# 12-Electrodes.net
KiCad netlist of a schematic drawn in Altium Designer
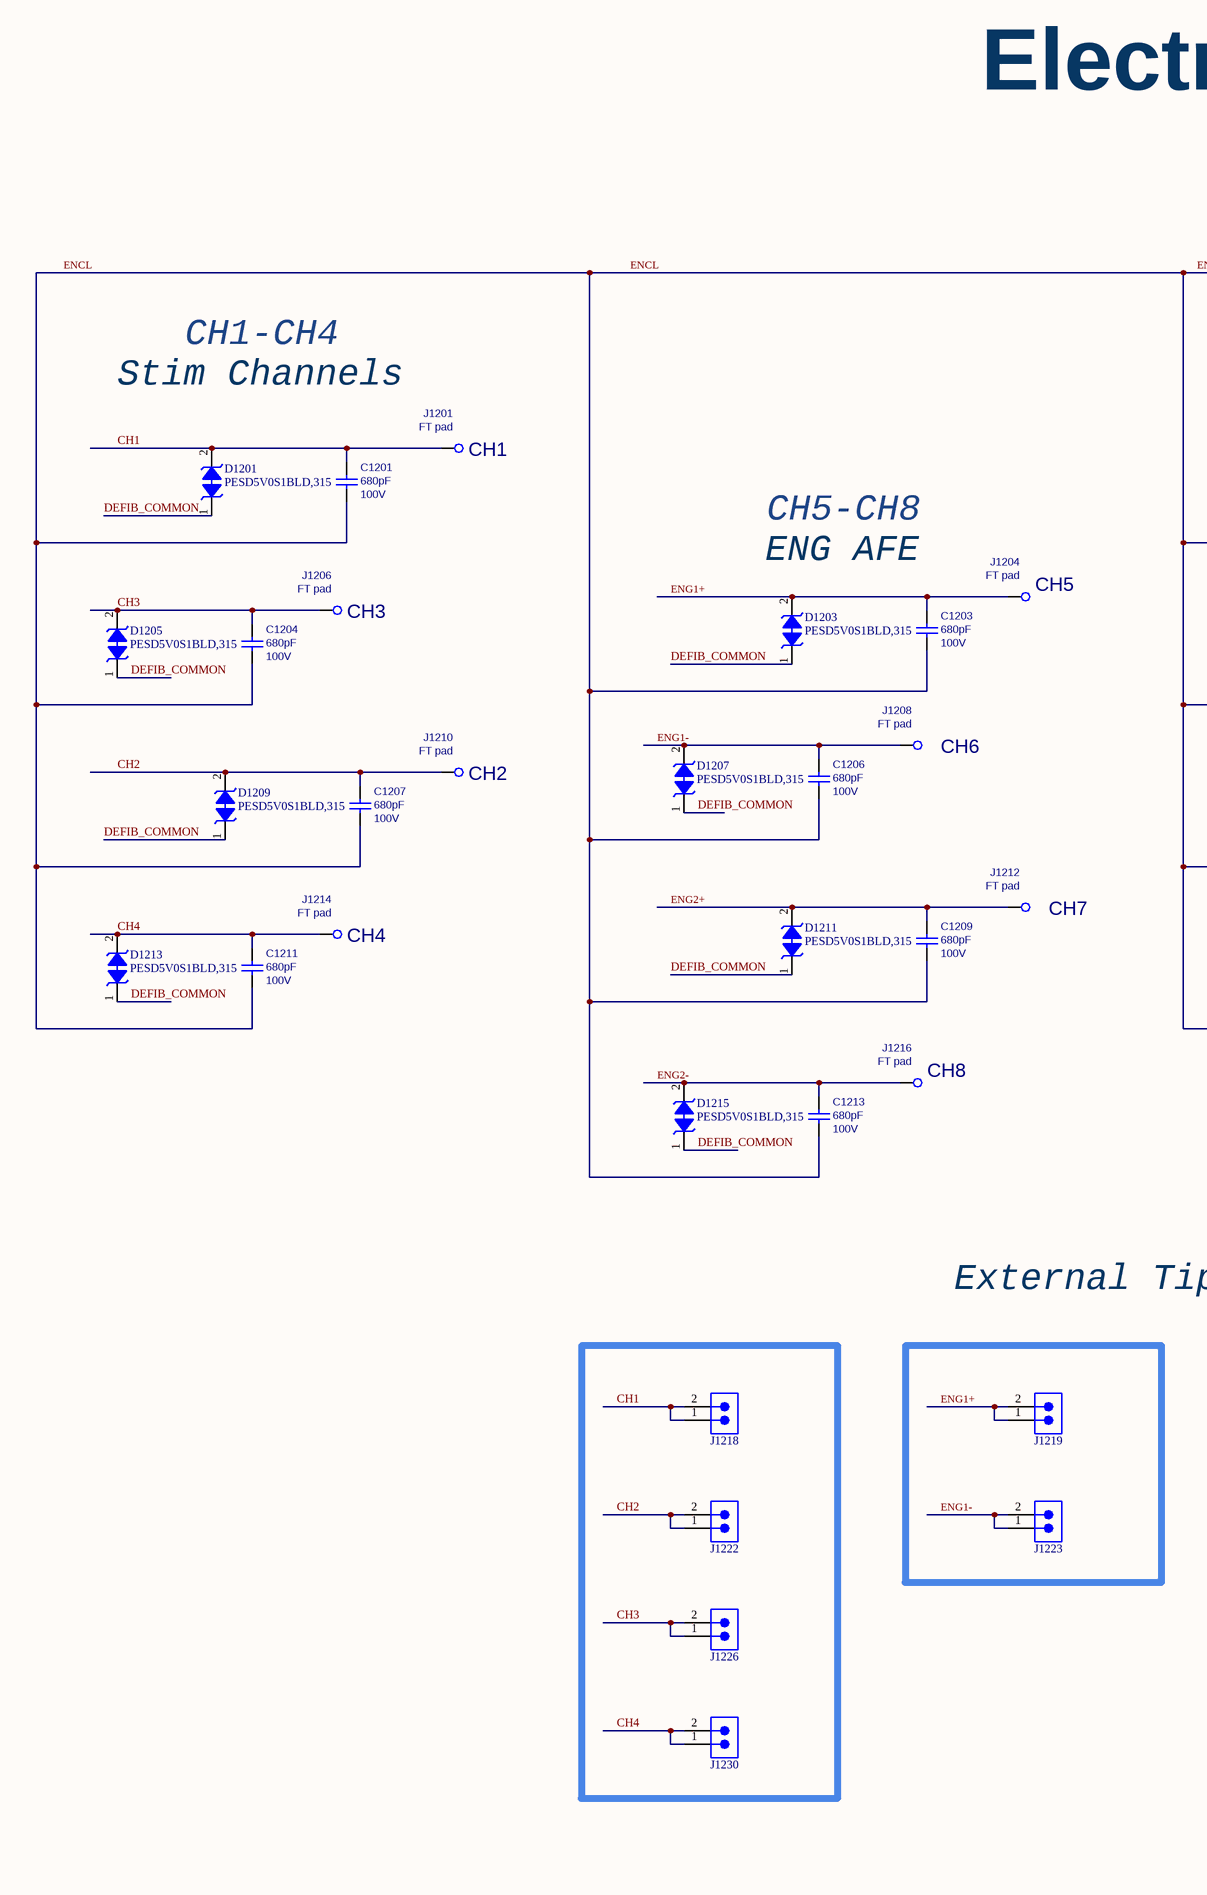
[diagram p0: 12-Electrodes.SchDoc, left]
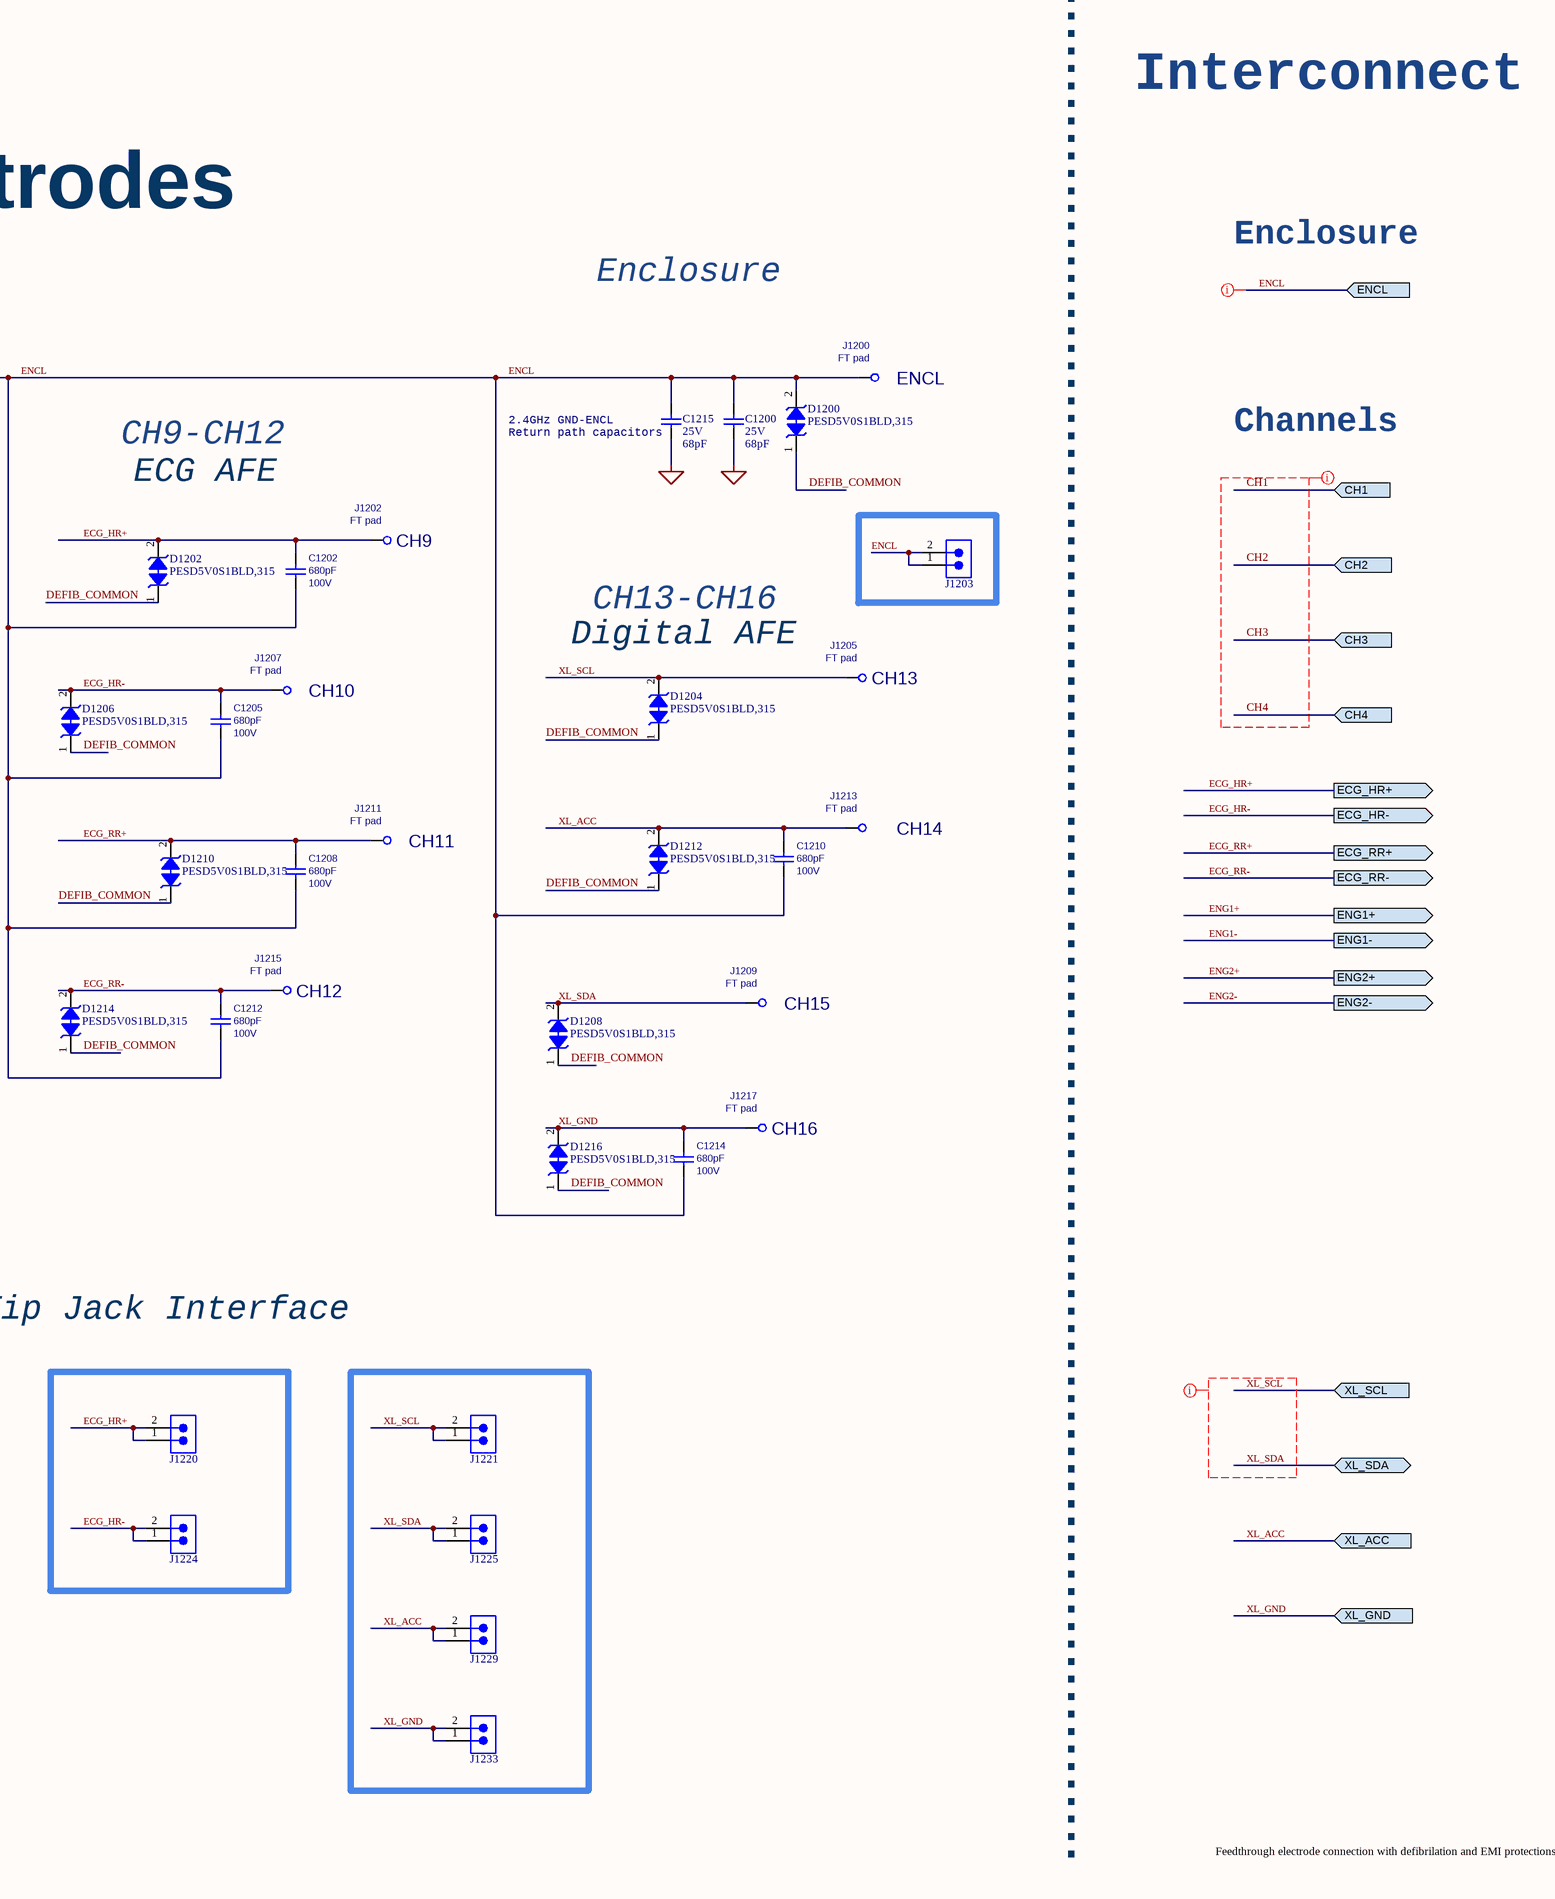
[diagram p1: 12-Electrodes.SchDoc, right]

(export (version "E")
  (design (tool "Eeschema 10.0.6"))
  (components
    (comp (ref "C1200")
      (value "68pF")
      (footprint "C0201_C")
      (description "Capacitor, 68pF, C0G, 25V, 5%, 0201, Implant-grade")
      (fields
        (field (name "MANUFACTURER") "Murata")
        (field (name "MANUFACTURER PART NUMBER") "GRT0335C1E680JA02D")
        (field (name "VOLTAGE RATING") "25V")
      )
      (libsource (lib "MP-LIBRARY") (part "GRT0335C1E680JA02D"))
    )
    (comp (ref "C1201")
      (value "680pF")
      (footprint "CAP0402_REDUCED")
      (description "Capacitor, 680pF, C0G, 100V, 5%, 0402")
      (fields
        (field (name "MANUFACTURER") "TDK")
        (field (name "RATING") "100V")
        (field (name "MANUFACTURER PART NUMBER") "C1005C0G2A681J050BE")
      )
      (libsource (lib "MP-LIBRARY") (part "C1005C0G2A681J050BE"))
    )
    (comp (ref "C1202")
      (value "680pF")
      (footprint "CAP0402_REDUCED")
      (description "Capacitor, 680pF, C0G, 100V, 5%, 0402")
      (fields
        (field (name "MANUFACTURER") "TDK")
        (field (name "RATING") "100V")
        (field (name "MANUFACTURER PART NUMBER") "C1005C0G2A681J050BE")
      )
      (libsource (lib "MP-LIBRARY") (part "C1005C0G2A681J050BE"))
    )
    (comp (ref "C1203")
      (value "680pF")
      (footprint "CAP0402_REDUCED")
      (description "Capacitor, 680pF, C0G, 100V, 5%, 0402")
      (fields
        (field (name "MANUFACTURER") "TDK")
        (field (name "RATING") "100V")
        (field (name "MANUFACTURER PART NUMBER") "C1005C0G2A681J050BE")
      )
      (libsource (lib "MP-LIBRARY") (part "C1005C0G2A681J050BE"))
    )
    (comp (ref "C1204")
      (value "680pF")
      (footprint "CAP0402_REDUCED")
      (description "Capacitor, 680pF, C0G, 100V, 5%, 0402")
      (fields
        (field (name "MANUFACTURER") "TDK")
        (field (name "RATING") "100V")
        (field (name "MANUFACTURER PART NUMBER") "C1005C0G2A681J050BE")
      )
      (libsource (lib "MP-LIBRARY") (part "C1005C0G2A681J050BE"))
    )
    (comp (ref "C1205")
      (value "680pF")
      (footprint "CAP0402_REDUCED")
      (description "Capacitor, 680pF, C0G, 100V, 5%, 0402")
      (fields
        (field (name "MANUFACTURER") "TDK")
        (field (name "RATING") "100V")
        (field (name "MANUFACTURER PART NUMBER") "C1005C0G2A681J050BE")
      )
      (libsource (lib "MP-LIBRARY") (part "C1005C0G2A681J050BE"))
    )
    (comp (ref "C1206")
      (value "680pF")
      (footprint "CAP0402_REDUCED")
      (description "Capacitor, 680pF, C0G, 100V, 5%, 0402")
      (fields
        (field (name "MANUFACTURER") "TDK")
        (field (name "RATING") "100V")
        (field (name "MANUFACTURER PART NUMBER") "C1005C0G2A681J050BE")
      )
      (libsource (lib "MP-LIBRARY") (part "C1005C0G2A681J050BE"))
    )
    (comp (ref "C1207")
      (value "680pF")
      (footprint "CAP0402_REDUCED")
      (description "Capacitor, 680pF, C0G, 100V, 5%, 0402")
      (fields
        (field (name "MANUFACTURER") "TDK")
        (field (name "RATING") "100V")
        (field (name "MANUFACTURER PART NUMBER") "C1005C0G2A681J050BE")
      )
      (libsource (lib "MP-LIBRARY") (part "C1005C0G2A681J050BE"))
    )
    (comp (ref "C1208")
      (value "680pF")
      (footprint "CAP0402_REDUCED")
      (description "Capacitor, 680pF, C0G, 100V, 5%, 0402")
      (fields
        (field (name "MANUFACTURER") "TDK")
        (field (name "RATING") "100V")
        (field (name "MANUFACTURER PART NUMBER") "C1005C0G2A681J050BE")
      )
      (libsource (lib "MP-LIBRARY") (part "C1005C0G2A681J050BE"))
    )
    (comp (ref "C1209")
      (value "680pF")
      (footprint "CAP0402_REDUCED")
      (description "Capacitor, 680pF, C0G, 100V, 5%, 0402")
      (fields
        (field (name "MANUFACTURER") "TDK")
        (field (name "RATING") "100V")
        (field (name "MANUFACTURER PART NUMBER") "C1005C0G2A681J050BE")
      )
      (libsource (lib "MP-LIBRARY") (part "C1005C0G2A681J050BE"))
    )
    (comp (ref "C1210")
      (value "680pF")
      (footprint "CAP0402_REDUCED")
      (description "Capacitor, 680pF, C0G, 100V, 5%, 0402")
      (fields
        (field (name "MANUFACTURER") "TDK")
        (field (name "RATING") "100V")
        (field (name "MANUFACTURER PART NUMBER") "C1005C0G2A681J050BE")
      )
      (libsource (lib "MP-LIBRARY") (part "C1005C0G2A681J050BE"))
    )
    (comp (ref "C1211")
      (value "680pF")
      (footprint "CAP0402_REDUCED")
      (description "Capacitor, 680pF, C0G, 100V, 5%, 0402")
      (fields
        (field (name "MANUFACTURER") "TDK")
        (field (name "RATING") "100V")
        (field (name "MANUFACTURER PART NUMBER") "C1005C0G2A681J050BE")
      )
      (libsource (lib "MP-LIBRARY") (part "C1005C0G2A681J050BE"))
    )
    (comp (ref "C1212")
      (value "680pF")
      (footprint "CAP0402_REDUCED")
      (description "Capacitor, 680pF, C0G, 100V, 5%, 0402")
      (fields
        (field (name "MANUFACTURER") "TDK")
        (field (name "RATING") "100V")
        (field (name "MANUFACTURER PART NUMBER") "C1005C0G2A681J050BE")
      )
      (libsource (lib "MP-LIBRARY") (part "C1005C0G2A681J050BE"))
    )
    (comp (ref "C1213")
      (value "680pF")
      (footprint "CAP0402_REDUCED")
      (description "Capacitor, 680pF, C0G, 100V, 5%, 0402")
      (fields
        (field (name "MANUFACTURER") "TDK")
        (field (name "RATING") "100V")
        (field (name "MANUFACTURER PART NUMBER") "C1005C0G2A681J050BE")
      )
      (libsource (lib "MP-LIBRARY") (part "C1005C0G2A681J050BE"))
    )
    (comp (ref "C1214")
      (value "680pF")
      (footprint "CAP0402_REDUCED")
      (description "Capacitor, 680pF, C0G, 100V, 5%, 0402")
      (fields
        (field (name "MANUFACTURER") "TDK")
        (field (name "RATING") "100V")
        (field (name "MANUFACTURER PART NUMBER") "C1005C0G2A681J050BE")
      )
      (libsource (lib "MP-LIBRARY") (part "C1005C0G2A681J050BE"))
    )
    (comp (ref "C1215")
      (value "68pF")
      (footprint "C0201_C")
      (description "Capacitor, 68pF, C0G, 25V, 5%, 0201, Implant-grade")
      (fields
        (field (name "MANUFACTURER") "Murata")
        (field (name "MANUFACTURER PART NUMBER") "GRT0335C1E680JA02D")
        (field (name "VOLTAGE RATING") "25V")
      )
      (libsource (lib "MP-LIBRARY") (part "GRT0335C1E680JA02D"))
    )
    (comp (ref "D1200")
      (value "PESD5V0S1BLD,315")
      (footprint "PESD5V0S1BLD315")
      (description "Diode ESD (Bi-directional)")
      (fields
        (field (name "MOUSER PART NUMBER") "771-PESD5V0S1BLD315")
        (field (name "MANUFACTURER") "Nexperia")
      )
      (libsource (lib "MP-LIBRARY") (part "PESD5V0S1BLD,315"))
    )
    (comp (ref "D1201")
      (value "PESD5V0S1BLD,315")
      (footprint "PESD5V0S1BLD315")
      (description "Diode ESD (Bi-directional)")
      (fields
        (field (name "MOUSER PART NUMBER") "771-PESD5V0S1BLD315")
        (field (name "MANUFACTURER") "Nexperia")
      )
      (libsource (lib "MP-LIBRARY") (part "PESD5V0S1BLD,315"))
    )
    (comp (ref "D1202")
      (value "PESD5V0S1BLD,315")
      (footprint "PESD5V0S1BLD315")
      (description "Diode ESD (Bi-directional)")
      (fields
        (field (name "MOUSER PART NUMBER") "771-PESD5V0S1BLD315")
        (field (name "MANUFACTURER") "Nexperia")
      )
      (libsource (lib "MP-LIBRARY") (part "PESD5V0S1BLD,315"))
    )
    (comp (ref "D1203")
      (value "PESD5V0S1BLD,315")
      (footprint "PESD5V0S1BLD315")
      (description "Diode ESD (Bi-directional)")
      (fields
        (field (name "MOUSER PART NUMBER") "771-PESD5V0S1BLD315")
        (field (name "MANUFACTURER") "Nexperia")
      )
      (libsource (lib "MP-LIBRARY") (part "PESD5V0S1BLD,315"))
    )
    (comp (ref "D1204")
      (value "PESD5V0S1BLD,315")
      (footprint "PESD5V0S1BLD315")
      (description "Diode ESD (Bi-directional)")
      (fields
        (field (name "MOUSER PART NUMBER") "771-PESD5V0S1BLD315")
        (field (name "MANUFACTURER") "Nexperia")
      )
      (libsource (lib "MP-LIBRARY") (part "PESD5V0S1BLD,315"))
    )
    (comp (ref "D1205")
      (value "PESD5V0S1BLD,315")
      (footprint "PESD5V0S1BLD315")
      (description "Diode ESD (Bi-directional)")
      (fields
        (field (name "MOUSER PART NUMBER") "771-PESD5V0S1BLD315")
        (field (name "MANUFACTURER") "Nexperia")
      )
      (libsource (lib "MP-LIBRARY") (part "PESD5V0S1BLD,315"))
    )
    (comp (ref "D1206")
      (value "PESD5V0S1BLD,315")
      (footprint "PESD5V0S1BLD315")
      (description "Diode ESD (Bi-directional)")
      (fields
        (field (name "MOUSER PART NUMBER") "771-PESD5V0S1BLD315")
        (field (name "MANUFACTURER") "Nexperia")
      )
      (libsource (lib "MP-LIBRARY") (part "PESD5V0S1BLD,315"))
    )
    (comp (ref "D1207")
      (value "PESD5V0S1BLD,315")
      (footprint "PESD5V0S1BLD315")
      (description "Diode ESD (Bi-directional)")
      (fields
        (field (name "MOUSER PART NUMBER") "771-PESD5V0S1BLD315")
        (field (name "MANUFACTURER") "Nexperia")
      )
      (libsource (lib "MP-LIBRARY") (part "PESD5V0S1BLD,315"))
    )
    (comp (ref "D1208")
      (value "PESD5V0S1BLD,315")
      (footprint "PESD5V0S1BLD315")
      (description "Diode ESD (Bi-directional)")
      (fields
        (field (name "MOUSER PART NUMBER") "771-PESD5V0S1BLD315")
        (field (name "MANUFACTURER") "Nexperia")
      )
      (libsource (lib "MP-LIBRARY") (part "PESD5V0S1BLD,315"))
    )
    (comp (ref "D1209")
      (value "PESD5V0S1BLD,315")
      (footprint "PESD5V0S1BLD315")
      (description "Diode ESD (Bi-directional)")
      (fields
        (field (name "MOUSER PART NUMBER") "771-PESD5V0S1BLD315")
        (field (name "MANUFACTURER") "Nexperia")
      )
      (libsource (lib "MP-LIBRARY") (part "PESD5V0S1BLD,315"))
    )
    (comp (ref "D1210")
      (value "PESD5V0S1BLD,315")
      (footprint "PESD5V0S1BLD315")
      (description "Diode ESD (Bi-directional)")
      (fields
        (field (name "MOUSER PART NUMBER") "771-PESD5V0S1BLD315")
        (field (name "MANUFACTURER") "Nexperia")
      )
      (libsource (lib "MP-LIBRARY") (part "PESD5V0S1BLD,315"))
    )
    (comp (ref "D1211")
      (value "PESD5V0S1BLD,315")
      (footprint "PESD5V0S1BLD315")
      (description "Diode ESD (Bi-directional)")
      (fields
        (field (name "MOUSER PART NUMBER") "771-PESD5V0S1BLD315")
        (field (name "MANUFACTURER") "Nexperia")
      )
      (libsource (lib "MP-LIBRARY") (part "PESD5V0S1BLD,315"))
    )
    (comp (ref "D1212")
      (value "PESD5V0S1BLD,315")
      (footprint "PESD5V0S1BLD315")
      (description "Diode ESD (Bi-directional)")
      (fields
        (field (name "MOUSER PART NUMBER") "771-PESD5V0S1BLD315")
        (field (name "MANUFACTURER") "Nexperia")
      )
      (libsource (lib "MP-LIBRARY") (part "PESD5V0S1BLD,315"))
    )
    (comp (ref "D1213")
      (value "PESD5V0S1BLD,315")
      (footprint "PESD5V0S1BLD315")
      (description "Diode ESD (Bi-directional)")
      (fields
        (field (name "MOUSER PART NUMBER") "771-PESD5V0S1BLD315")
        (field (name "MANUFACTURER") "Nexperia")
      )
      (libsource (lib "MP-LIBRARY") (part "PESD5V0S1BLD,315"))
    )
    (comp (ref "D1214")
      (value "PESD5V0S1BLD,315")
      (footprint "PESD5V0S1BLD315")
      (description "Diode ESD (Bi-directional)")
      (fields
        (field (name "MOUSER PART NUMBER") "771-PESD5V0S1BLD315")
        (field (name "MANUFACTURER") "Nexperia")
      )
      (libsource (lib "MP-LIBRARY") (part "PESD5V0S1BLD,315"))
    )
    (comp (ref "D1215")
      (value "PESD5V0S1BLD,315")
      (footprint "PESD5V0S1BLD315")
      (description "Diode ESD (Bi-directional)")
      (fields
        (field (name "MOUSER PART NUMBER") "771-PESD5V0S1BLD315")
        (field (name "MANUFACTURER") "Nexperia")
      )
      (libsource (lib "MP-LIBRARY") (part "PESD5V0S1BLD,315"))
    )
    (comp (ref "D1216")
      (value "PESD5V0S1BLD,315")
      (footprint "PESD5V0S1BLD315")
      (description "Diode ESD (Bi-directional)")
      (fields
        (field (name "MOUSER PART NUMBER") "771-PESD5V0S1BLD315")
        (field (name "MANUFACTURER") "Nexperia")
      )
      (libsource (lib "MP-LIBRARY") (part "PESD5V0S1BLD,315"))
    )
    (comp (ref "J1200")
      (value "FT pad")
      (footprint "FEEDHOLE_20mil")
      (description "FT pad, Thru-hole, 20 mil hole")
      (fields (field (name "Comment") "THPAD_20m"))
      (libsource (lib "MP-LIBRARY") (part "HOLE_20m"))
    )
    (comp (ref "J1201")
      (value "FT pad")
      (footprint "FEEDHOLE_20mil")
      (description "FT pad, Thru-hole, 20 mil hole")
      (fields (field (name "Comment") "THPAD_20m"))
      (libsource (lib "MP-LIBRARY") (part "HOLE_20m"))
    )
    (comp (ref "J1202")
      (value "FT pad")
      (footprint "FEEDHOLE_20mil")
      (description "FT pad, Thru-hole, 20 mil hole")
      (fields (field (name "Comment") "THPAD_20m"))
      (libsource (lib "MP-LIBRARY") (part "HOLE_20m"))
    )
    (comp (ref "J1203")
      (value "TSW-102-26-G-S")
      (footprint "SMTC-TSW-102-26-XX-S")
      (description "Conn Unshrouded Header HDR 2 POS 2.54mm Solder ST Thru-Hole")
      (fields (field (name "MANUFACTURER") "Samtec"))
      (libsource (lib "MP-LIBRARY") (part "TSW-102-26-G-S"))
    )
    (comp (ref "J1204")
      (value "FT pad")
      (footprint "FEEDHOLE_20mil")
      (description "FT pad, Thru-hole, 20 mil hole")
      (fields (field (name "Comment") "THPAD_20m"))
      (libsource (lib "MP-LIBRARY") (part "HOLE_20m"))
    )
    (comp (ref "J1205")
      (value "FT pad")
      (footprint "FEEDHOLE_20mil")
      (description "FT pad, Thru-hole, 20 mil hole")
      (fields (field (name "Comment") "THPAD_20m"))
      (libsource (lib "MP-LIBRARY") (part "HOLE_20m"))
    )
    (comp (ref "J1206")
      (value "FT pad")
      (footprint "FEEDHOLE_20mil")
      (description "FT pad, Thru-hole, 20 mil hole")
      (fields (field (name "Comment") "THPAD_20m"))
      (libsource (lib "MP-LIBRARY") (part "HOLE_20m"))
    )
    (comp (ref "J1207")
      (value "FT pad")
      (footprint "FEEDHOLE_20mil")
      (description "FT pad, Thru-hole, 20 mil hole")
      (fields (field (name "Comment") "THPAD_20m"))
      (libsource (lib "MP-LIBRARY") (part "HOLE_20m"))
    )
    (comp (ref "J1208")
      (value "FT pad")
      (footprint "FEEDHOLE_20mil")
      (description "FT pad, Thru-hole, 20 mil hole")
      (fields (field (name "Comment") "THPAD_20m"))
      (libsource (lib "MP-LIBRARY") (part "HOLE_20m"))
    )
    (comp (ref "J1209")
      (value "FT pad")
      (footprint "FEEDHOLE_20mil")
      (description "FT pad, Thru-hole, 20 mil hole")
      (fields (field (name "Comment") "THPAD_20m"))
      (libsource (lib "MP-LIBRARY") (part "HOLE_20m"))
    )
    (comp (ref "J1210")
      (value "FT pad")
      (footprint "FEEDHOLE_20mil")
      (description "FT pad, Thru-hole, 20 mil hole")
      (fields (field (name "Comment") "THPAD_20m"))
      (libsource (lib "MP-LIBRARY") (part "HOLE_20m"))
    )
    (comp (ref "J1211")
      (value "FT pad")
      (footprint "FEEDHOLE_20mil")
      (description "FT pad, Thru-hole, 20 mil hole")
      (fields (field (name "Comment") "THPAD_20m"))
      (libsource (lib "MP-LIBRARY") (part "HOLE_20m"))
    )
    (comp (ref "J1212")
      (value "FT pad")
      (footprint "FEEDHOLE_20mil")
      (description "FT pad, Thru-hole, 20 mil hole")
      (fields (field (name "Comment") "THPAD_20m"))
      (libsource (lib "MP-LIBRARY") (part "HOLE_20m"))
    )
    (comp (ref "J1213")
      (value "FT pad")
      (footprint "FEEDHOLE_20mil")
      (description "FT pad, Thru-hole, 20 mil hole")
      (fields (field (name "Comment") "THPAD_20m"))
      (libsource (lib "MP-LIBRARY") (part "HOLE_20m"))
    )
    (comp (ref "J1214")
      (value "FT pad")
      (footprint "FEEDHOLE_20mil")
      (description "FT pad, Thru-hole, 20 mil hole")
      (fields (field (name "Comment") "THPAD_20m"))
      (libsource (lib "MP-LIBRARY") (part "HOLE_20m"))
    )
    (comp (ref "J1215")
      (value "FT pad")
      (footprint "FEEDHOLE_20mil")
      (description "FT pad, Thru-hole, 20 mil hole")
      (fields (field (name "Comment") "THPAD_20m"))
      (libsource (lib "MP-LIBRARY") (part "HOLE_20m"))
    )
    (comp (ref "J1216")
      (value "FT pad")
      (footprint "FEEDHOLE_20mil")
      (description "FT pad, Thru-hole, 20 mil hole")
      (fields (field (name "Comment") "THPAD_20m"))
      (libsource (lib "MP-LIBRARY") (part "HOLE_20m"))
    )
    (comp (ref "J1217")
      (value "FT pad")
      (footprint "FEEDHOLE_20mil")
      (description "FT pad, Thru-hole, 20 mil hole")
      (fields (field (name "Comment") "THPAD_20m"))
      (libsource (lib "MP-LIBRARY") (part "HOLE_20m"))
    )
    (comp (ref "J1218")
      (value "TSW-102-26-G-S")
      (footprint "SMTC-TSW-102-26-XX-S")
      (description "Conn Unshrouded Header HDR 2 POS 2.54mm Solder ST Thru-Hole")
      (fields (field (name "MANUFACTURER") "Samtec"))
      (libsource (lib "MP-LIBRARY") (part "TSW-102-26-G-S"))
    )
    (comp (ref "J1219")
      (value "TSW-102-26-G-S")
      (footprint "SMTC-TSW-102-26-XX-S")
      (description "Conn Unshrouded Header HDR 2 POS 2.54mm Solder ST Thru-Hole")
      (fields (field (name "MANUFACTURER") "Samtec"))
      (libsource (lib "MP-LIBRARY") (part "TSW-102-26-G-S"))
    )
    (comp (ref "J1220")
      (value "TSW-102-26-G-S")
      (footprint "SMTC-TSW-102-26-XX-S")
      (description "Conn Unshrouded Header HDR 2 POS 2.54mm Solder ST Thru-Hole")
      (fields (field (name "MANUFACTURER") "Samtec"))
      (libsource (lib "MP-LIBRARY") (part "TSW-102-26-G-S"))
    )
    (comp (ref "J1221")
      (value "TSW-102-26-G-S")
      (footprint "SMTC-TSW-102-26-XX-S")
      (description "Conn Unshrouded Header HDR 2 POS 2.54mm Solder ST Thru-Hole")
      (fields (field (name "MANUFACTURER") "Samtec"))
      (libsource (lib "MP-LIBRARY") (part "TSW-102-26-G-S"))
    )
    (comp (ref "J1222")
      (value "TSW-102-26-G-S")
      (footprint "SMTC-TSW-102-26-XX-S")
      (description "Conn Unshrouded Header HDR 2 POS 2.54mm Solder ST Thru-Hole")
      (fields (field (name "MANUFACTURER") "Samtec"))
      (libsource (lib "MP-LIBRARY") (part "TSW-102-26-G-S"))
    )
    (comp (ref "J1223")
      (value "TSW-102-26-G-S")
      (footprint "SMTC-TSW-102-26-XX-S")
      (description "Conn Unshrouded Header HDR 2 POS 2.54mm Solder ST Thru-Hole")
      (fields (field (name "MANUFACTURER") "Samtec"))
      (libsource (lib "MP-LIBRARY") (part "TSW-102-26-G-S"))
    )
    (comp (ref "J1224")
      (value "TSW-102-26-G-S")
      (footprint "SMTC-TSW-102-26-XX-S")
      (description "Conn Unshrouded Header HDR 2 POS 2.54mm Solder ST Thru-Hole")
      (fields (field (name "MANUFACTURER") "Samtec"))
      (libsource (lib "MP-LIBRARY") (part "TSW-102-26-G-S"))
    )
    (comp (ref "J1225")
      (value "TSW-102-26-G-S")
      (footprint "SMTC-TSW-102-26-XX-S")
      (description "Conn Unshrouded Header HDR 2 POS 2.54mm Solder ST Thru-Hole")
      (fields (field (name "MANUFACTURER") "Samtec"))
      (libsource (lib "MP-LIBRARY") (part "TSW-102-26-G-S"))
    )
    (comp (ref "J1226")
      (value "TSW-102-26-G-S")
      (footprint "SMTC-TSW-102-26-XX-S")
      (description "Conn Unshrouded Header HDR 2 POS 2.54mm Solder ST Thru-Hole")
      (fields (field (name "MANUFACTURER") "Samtec"))
      (libsource (lib "MP-LIBRARY") (part "TSW-102-26-G-S"))
    )
    (comp (ref "J1229")
      (value "TSW-102-26-G-S")
      (footprint "SMTC-TSW-102-26-XX-S")
      (description "Conn Unshrouded Header HDR 2 POS 2.54mm Solder ST Thru-Hole")
      (fields (field (name "MANUFACTURER") "Samtec"))
      (libsource (lib "MP-LIBRARY") (part "TSW-102-26-G-S"))
    )
    (comp (ref "J1230")
      (value "TSW-102-26-G-S")
      (footprint "SMTC-TSW-102-26-XX-S")
      (description "Conn Unshrouded Header HDR 2 POS 2.54mm Solder ST Thru-Hole")
      (fields (field (name "MANUFACTURER") "Samtec"))
      (libsource (lib "MP-LIBRARY") (part "TSW-102-26-G-S"))
    )
    (comp (ref "J1233")
      (value "TSW-102-26-G-S")
      (footprint "SMTC-TSW-102-26-XX-S")
      (description "Conn Unshrouded Header HDR 2 POS 2.54mm Solder ST Thru-Hole")
      (fields (field (name "MANUFACTURER") "Samtec"))
      (libsource (lib "MP-LIBRARY") (part "TSW-102-26-G-S"))
    )
  )
  (nets
    (net (code "1") (name "/CH1") (class "Default")
      (node (ref "C1201") (pin "2") (pinfunction "2_2") (pintype "passive"))
      (node (ref "D1201") (pin "2") (pinfunction "K2_2") (pintype "passive"))
      (node (ref "J1201") (pin "1") (pinfunction "1_1") (pintype "passive"))
      (node (ref "J1218") (pin "1") (pinfunction "1_1") (pintype "passive"))
      (node (ref "J1218") (pin "2") (pinfunction "2_2") (pintype "passive"))
    )
    (net (code "2") (name "/CH2") (class "Default")
      (node (ref "C1207") (pin "2") (pinfunction "2_2") (pintype "passive"))
      (node (ref "D1209") (pin "2") (pinfunction "K2_2") (pintype "passive"))
      (node (ref "J1210") (pin "1") (pinfunction "1_1") (pintype "passive"))
      (node (ref "J1222") (pin "1") (pinfunction "1_1") (pintype "passive"))
      (node (ref "J1222") (pin "2") (pinfunction "2_2") (pintype "passive"))
    )
    (net (code "3") (name "/CH3") (class "Default")
      (node (ref "C1204") (pin "2") (pinfunction "2_2") (pintype "passive"))
      (node (ref "D1205") (pin "2") (pinfunction "K2_2") (pintype "passive"))
      (node (ref "J1206") (pin "1") (pinfunction "1_1") (pintype "passive"))
      (node (ref "J1226") (pin "1") (pinfunction "1_1") (pintype "passive"))
      (node (ref "J1226") (pin "2") (pinfunction "2_2") (pintype "passive"))
    )
    (net (code "4") (name "/CH4") (class "Default")
      (node (ref "C1211") (pin "2") (pinfunction "2_2") (pintype "passive"))
      (node (ref "D1213") (pin "2") (pinfunction "K2_2") (pintype "passive"))
      (node (ref "J1214") (pin "1") (pinfunction "1_1") (pintype "passive"))
      (node (ref "J1230") (pin "1") (pinfunction "1_1") (pintype "passive"))
      (node (ref "J1230") (pin "2") (pinfunction "2_2") (pintype "passive"))
    )
    (net (code "5") (name "/DEFIB_COMMON") (class "Default")
      (node (ref "D1200") (pin "1") (pinfunction "K1_1") (pintype "passive"))
      (node (ref "D1201") (pin "1") (pinfunction "K1_1") (pintype "passive"))
      (node (ref "D1202") (pin "1") (pinfunction "K1_1") (pintype "passive"))
      (node (ref "D1203") (pin "1") (pinfunction "K1_1") (pintype "passive"))
      (node (ref "D1204") (pin "1") (pinfunction "K1_1") (pintype "passive"))
      (node (ref "D1205") (pin "1") (pinfunction "K1_1") (pintype "passive"))
      (node (ref "D1206") (pin "1") (pinfunction "K1_1") (pintype "passive"))
      (node (ref "D1207") (pin "1") (pinfunction "K1_1") (pintype "passive"))
      (node (ref "D1208") (pin "1") (pinfunction "K1_1") (pintype "passive"))
      (node (ref "D1209") (pin "1") (pinfunction "K1_1") (pintype "passive"))
      (node (ref "D1210") (pin "1") (pinfunction "K1_1") (pintype "passive"))
      (node (ref "D1211") (pin "1") (pinfunction "K1_1") (pintype "passive"))
      (node (ref "D1212") (pin "1") (pinfunction "K1_1") (pintype "passive"))
      (node (ref "D1213") (pin "1") (pinfunction "K1_1") (pintype "passive"))
      (node (ref "D1214") (pin "1") (pinfunction "K1_1") (pintype "passive"))
      (node (ref "D1215") (pin "1") (pinfunction "K1_1") (pintype "passive"))
      (node (ref "D1216") (pin "1") (pinfunction "K1_1") (pintype "passive"))
    )
    (net (code "6") (name "/ECG_HR+") (class "Default")
      (node (ref "C1202") (pin "2") (pinfunction "2_2") (pintype "passive"))
      (node (ref "D1202") (pin "2") (pinfunction "K2_2") (pintype "passive"))
      (node (ref "J1202") (pin "1") (pinfunction "1_1") (pintype "passive"))
      (node (ref "J1220") (pin "1") (pinfunction "1_1") (pintype "passive"))
      (node (ref "J1220") (pin "2") (pinfunction "2_2") (pintype "passive"))
    )
    (net (code "7") (name "/ECG_HR-") (class "Default")
      (node (ref "C1205") (pin "2") (pinfunction "2_2") (pintype "passive"))
      (node (ref "D1206") (pin "2") (pinfunction "K2_2") (pintype "passive"))
      (node (ref "J1207") (pin "1") (pinfunction "1_1") (pintype "passive"))
      (node (ref "J1224") (pin "1") (pinfunction "1_1") (pintype "passive"))
      (node (ref "J1224") (pin "2") (pinfunction "2_2") (pintype "passive"))
    )
    (net (code "8") (name "/ECG_RR+") (class "Default")
      (node (ref "C1208") (pin "2") (pinfunction "2_2") (pintype "passive"))
      (node (ref "D1210") (pin "2") (pinfunction "K2_2") (pintype "passive"))
      (node (ref "J1211") (pin "1") (pinfunction "1_1") (pintype "passive"))
    )
    (net (code "9") (name "/ECG_RR-") (class "Default")
      (node (ref "C1212") (pin "2") (pinfunction "2_2") (pintype "passive"))
      (node (ref "D1214") (pin "2") (pinfunction "K2_2") (pintype "passive"))
      (node (ref "J1215") (pin "1") (pinfunction "1_1") (pintype "passive"))
    )
    (net (code "10") (name "/ENCL") (class "Default")
      (node (ref "C1200") (pin "2") (pinfunction "2_2") (pintype "passive"))
      (node (ref "C1201") (pin "1") (pinfunction "1_1") (pintype "passive"))
      (node (ref "C1202") (pin "1") (pinfunction "1_1") (pintype "passive"))
      (node (ref "C1203") (pin "1") (pinfunction "1_1") (pintype "passive"))
      (node (ref "C1204") (pin "1") (pinfunction "1_1") (pintype "passive"))
      (node (ref "C1205") (pin "1") (pinfunction "1_1") (pintype "passive"))
      (node (ref "C1206") (pin "1") (pinfunction "1_1") (pintype "passive"))
      (node (ref "C1207") (pin "1") (pinfunction "1_1") (pintype "passive"))
      (node (ref "C1208") (pin "1") (pinfunction "1_1") (pintype "passive"))
      (node (ref "C1209") (pin "1") (pinfunction "1_1") (pintype "passive"))
      (node (ref "C1210") (pin "1") (pinfunction "1_1") (pintype "passive"))
      (node (ref "C1211") (pin "1") (pinfunction "1_1") (pintype "passive"))
      (node (ref "C1212") (pin "1") (pinfunction "1_1") (pintype "passive"))
      (node (ref "C1213") (pin "1") (pinfunction "1_1") (pintype "passive"))
      (node (ref "C1214") (pin "1") (pinfunction "1_1") (pintype "passive"))
      (node (ref "C1215") (pin "2") (pinfunction "2_2") (pintype "passive"))
      (node (ref "D1200") (pin "2") (pinfunction "K2_2") (pintype "passive"))
      (node (ref "J1200") (pin "1") (pinfunction "1_1") (pintype "passive"))
      (node (ref "J1203") (pin "1") (pinfunction "1_1") (pintype "passive"))
      (node (ref "J1203") (pin "2") (pinfunction "2_2") (pintype "passive"))
    )
    (net (code "11") (name "/ENG1+") (class "Default")
      (node (ref "C1203") (pin "2") (pinfunction "2_2") (pintype "passive"))
      (node (ref "D1203") (pin "2") (pinfunction "K2_2") (pintype "passive"))
      (node (ref "J1204") (pin "1") (pinfunction "1_1") (pintype "passive"))
      (node (ref "J1219") (pin "1") (pinfunction "1_1") (pintype "passive"))
      (node (ref "J1219") (pin "2") (pinfunction "2_2") (pintype "passive"))
    )
    (net (code "12") (name "/ENG1-") (class "Default")
      (node (ref "C1206") (pin "2") (pinfunction "2_2") (pintype "passive"))
      (node (ref "D1207") (pin "2") (pinfunction "K2_2") (pintype "passive"))
      (node (ref "J1208") (pin "1") (pinfunction "1_1") (pintype "passive"))
      (node (ref "J1223") (pin "1") (pinfunction "1_1") (pintype "passive"))
      (node (ref "J1223") (pin "2") (pinfunction "2_2") (pintype "passive"))
    )
    (net (code "13") (name "/ENG2+") (class "Default")
      (node (ref "C1209") (pin "2") (pinfunction "2_2") (pintype "passive"))
      (node (ref "D1211") (pin "2") (pinfunction "K2_2") (pintype "passive"))
      (node (ref "J1212") (pin "1") (pinfunction "1_1") (pintype "passive"))
    )
    (net (code "14") (name "/ENG2-") (class "Default")
      (node (ref "C1213") (pin "2") (pinfunction "2_2") (pintype "passive"))
      (node (ref "D1215") (pin "2") (pinfunction "K2_2") (pintype "passive"))
      (node (ref "J1216") (pin "1") (pinfunction "1_1") (pintype "passive"))
    )
    (net (code "15") (name "/XL_ACC") (class "Default")
      (node (ref "C1210") (pin "2") (pinfunction "2_2") (pintype "passive"))
      (node (ref "D1212") (pin "2") (pinfunction "K2_2") (pintype "passive"))
      (node (ref "J1213") (pin "1") (pinfunction "1_1") (pintype "passive"))
      (node (ref "J1229") (pin "1") (pinfunction "1_1") (pintype "passive"))
      (node (ref "J1229") (pin "2") (pinfunction "2_2") (pintype "passive"))
    )
    (net (code "16") (name "/XL_GND") (class "Default")
      (node (ref "C1214") (pin "2") (pinfunction "2_2") (pintype "passive"))
      (node (ref "D1216") (pin "2") (pinfunction "K2_2") (pintype "passive"))
      (node (ref "J1217") (pin "1") (pinfunction "1_1") (pintype "passive"))
      (node (ref "J1233") (pin "1") (pinfunction "1_1") (pintype "passive"))
      (node (ref "J1233") (pin "2") (pinfunction "2_2") (pintype "passive"))
    )
    (net (code "17") (name "/XL_SCL") (class "Default")
      (node (ref "D1204") (pin "2") (pinfunction "K2_2") (pintype "passive"))
      (node (ref "J1205") (pin "1") (pinfunction "1_1") (pintype "passive"))
      (node (ref "J1221") (pin "1") (pinfunction "1_1") (pintype "passive"))
      (node (ref "J1221") (pin "2") (pinfunction "2_2") (pintype "passive"))
    )
    (net (code "18") (name "/XL_SDA") (class "Default")
      (node (ref "D1208") (pin "2") (pinfunction "K2_2") (pintype "passive"))
      (node (ref "J1209") (pin "1") (pinfunction "1_1") (pintype "passive"))
      (node (ref "J1225") (pin "1") (pinfunction "1_1") (pintype "passive"))
      (node (ref "J1225") (pin "2") (pinfunction "2_2") (pintype "passive"))
    )
    (net (code "19") (name "GND") (class "Default")
      (node (ref "C1200") (pin "1") (pinfunction "1_1") (pintype "passive"))
      (node (ref "C1215") (pin "1") (pinfunction "1_1") (pintype "passive"))
    )
  )
)
